# delay_width.net
KiCad netlist of a schematic drawn in Altium Designer
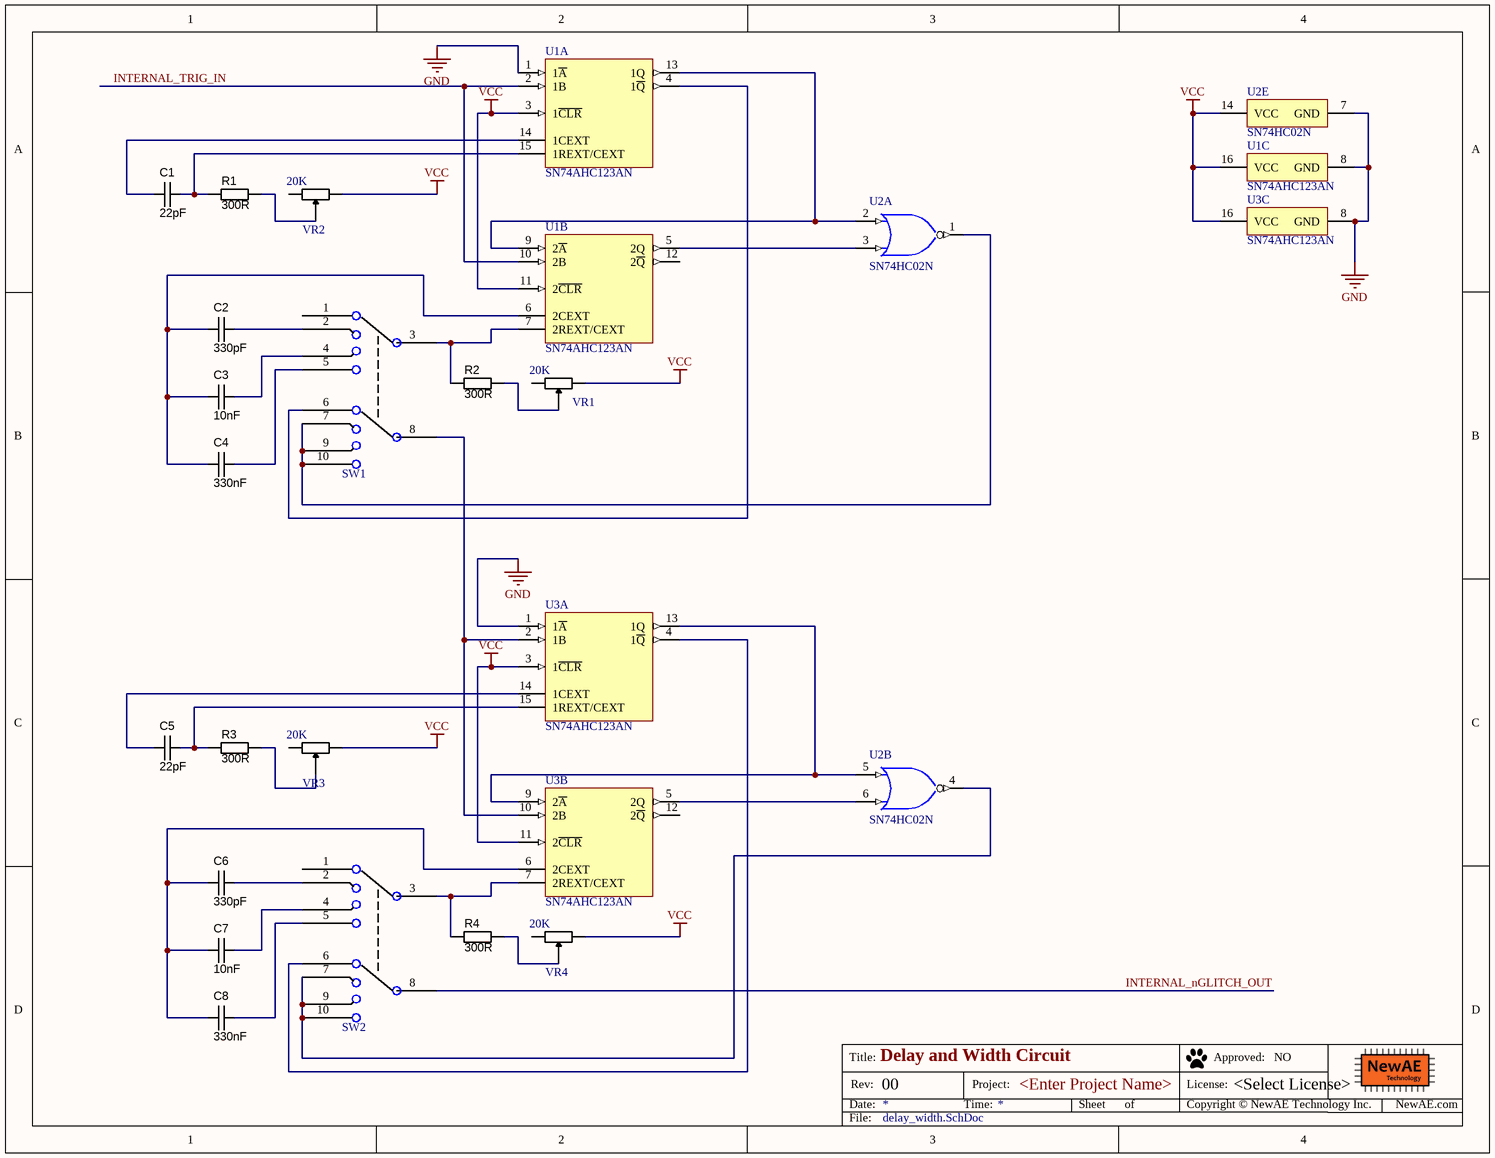
[diagram p0: delay_width.SchDoc]

(export (version "E")
  (design (tool "Eeschema 10.0.6"))
  (components
    (comp (ref "C1")
      (value "22pF")
      (footprint "CAPC500P450250X550")
      (description "Capacitor Ceramic 220nF 10% 50V X7R radial 5mm lead spacing")
      (fields (field (name "TOLERANCE") "±10%") (field (name "Comment") "approved sub OK"))
      (libsource (lib "PBL - Capacitors") (part "CAPR_220n_Radial_5mm"))
    )
    (comp (ref "C2")
      (value "330pF")
      (footprint "CAPC500P450250X550")
      (description "Capacitor Ceramic 220nF 10% 50V X7R radial 5mm lead spacing")
      (fields (field (name "TOLERANCE") "±10%") (field (name "Comment") "approved sub OK"))
      (libsource (lib "PBL - Capacitors") (part "CAPR_220n_Radial_5mm"))
    )
    (comp (ref "C3")
      (value "10nF")
      (footprint "CAPC500P450250X550")
      (description "Capacitor Ceramic 220nF 10% 50V X7R radial 5mm lead spacing")
      (fields (field (name "TOLERANCE") "±10%") (field (name "Comment") "approved sub OK"))
      (libsource (lib "PBL - Capacitors") (part "CAPR_220n_Radial_5mm"))
    )
    (comp (ref "C4")
      (value "330nF")
      (footprint "CAPC500P450250X550")
      (description "Capacitor Ceramic 220nF 10% 50V X7R radial 5mm lead spacing")
      (fields (field (name "TOLERANCE") "±10%") (field (name "Comment") "approved sub OK"))
      (libsource (lib "PBL - Capacitors") (part "CAPR_220n_Radial_5mm"))
    )
    (comp (ref "C5")
      (value "22pF")
      (footprint "CAPC500P450250X550")
      (description "Capacitor Ceramic 220nF 10% 50V X7R radial 5mm lead spacing")
      (fields (field (name "TOLERANCE") "±10%") (field (name "Comment") "approved sub OK"))
      (libsource (lib "PBL - Capacitors") (part "CAPR_220n_Radial_5mm"))
    )
    (comp (ref "C6")
      (value "330pF")
      (footprint "CAPC500P450250X550")
      (description "Capacitor Ceramic 220nF 10% 50V X7R radial 5mm lead spacing")
      (fields (field (name "TOLERANCE") "±10%") (field (name "Comment") "approved sub OK"))
      (libsource (lib "PBL - Capacitors") (part "CAPR_220n_Radial_5mm"))
    )
    (comp (ref "C7")
      (value "10nF")
      (footprint "CAPC500P450250X550")
      (description "Capacitor Ceramic 220nF 10% 50V X7R radial 5mm lead spacing")
      (fields (field (name "TOLERANCE") "±10%") (field (name "Comment") "approved sub OK"))
      (libsource (lib "PBL - Capacitors") (part "CAPR_220n_Radial_5mm"))
    )
    (comp (ref "C8")
      (value "330nF")
      (footprint "CAPC500P450250X550")
      (description "Capacitor Ceramic 220nF 10% 50V X7R radial 5mm lead spacing")
      (fields (field (name "TOLERANCE") "±10%") (field (name "Comment") "approved sub OK"))
      (libsource (lib "PBL - Capacitors") (part "CAPR_220n_Radial_5mm"))
    )
    (comp (ref "R1")
      (value "300R")
      (footprint "RESTH_AXIAL-0.4")
      (description "Resistor THD Axial 220 Ohm 0.25W 5% Carbon Film")
      (fields (field (name "TOLERANCE") "±5%") (field (name "Comment") "Carbon Film"))
      (libsource (lib "PBL - Resistors") (part "RES_220R_Axial_0.25W_5%"))
    )
    (comp (ref "R2")
      (value "300R")
      (footprint "RESTH_AXIAL-0.4")
      (description "Resistor THD Axial 220 Ohm 0.25W 5% Carbon Film")
      (fields (field (name "TOLERANCE") "±5%") (field (name "Comment") "Carbon Film"))
      (libsource (lib "PBL - Resistors") (part "RES_220R_Axial_0.25W_5%"))
    )
    (comp (ref "R3")
      (value "300R")
      (footprint "RESTH_AXIAL-0.4")
      (description "Resistor THD Axial 220 Ohm 0.25W 5% Carbon Film")
      (fields (field (name "TOLERANCE") "±5%") (field (name "Comment") "Carbon Film"))
      (libsource (lib "PBL - Resistors") (part "RES_220R_Axial_0.25W_5%"))
    )
    (comp (ref "R4")
      (value "300R")
      (footprint "RESTH_AXIAL-0.4")
      (description "Resistor THD Axial 220 Ohm 0.25W 5% Carbon Film")
      (fields (field (name "TOLERANCE") "±5%") (field (name "Comment") "Carbon Film"))
      (libsource (lib "PBL - Resistors") (part "RES_220R_Axial_0.25W_5%"))
    )
    (comp (ref "SW1")
      (value "SS-24E06-TG 5 (P)")
      (footprint "CK_SS24E06TG5P")
      (description "2P4T Slide, C&K Through Hole")
      (fields (field (name "PART NUMBER") "SS24E06TG5P"))
      (libsource (lib "NewAE_AltiumLib") (part "SW_2P4T_SS24E06TG5P"))
    )
    (comp (ref "SW2")
      (value "SS-24E06-TG 5 (P)")
      (footprint "CK_SS24E06TG5P")
      (description "2P4T Slide, C&K Through Hole")
      (fields (field (name "PART NUMBER") "SS24E06TG5P"))
      (libsource (lib "NewAE_AltiumLib") (part "SW_2P4T_SS24E06TG5P"))
    )
    (comp (ref "U1")
      (value "SN74AHC123AN")
      (footprint "N0016A")
      (description "Dual Retriggerable Monostable Multivibrators, N0016A, TUBE")
      (fields
        (field (name "GENERIC PART NUMBER") "SN74AHC123A")
        (field (name "MANUFACTURER") "Texas Instruments")
      )
      (libsource (lib "Altium Content Vault") (part "TI-SNX4XXXX123A_74LV221A-16"))
    )
    (comp (ref "U2")
      (value "SN74HC02N")
      (footprint "N0014A")
      (description "Quadruple 2-Input Positive-NOR Gates, N0014A, TUBE")
      (fields
        (field (name "MANUFACTURER") "Texas Instruments")
        (field (name "GENERIC PART NUMBER") "SN74HC02")
      )
      (libsource (lib "Altium Content Vault") (part "TI-NOR-4-2IN-14"))
    )
    (comp (ref "U3")
      (value "SN74AHC123AN")
      (footprint "N0016A")
      (description "Dual Retriggerable Monostable Multivibrators, N0016A, TUBE")
      (fields
        (field (name "GENERIC PART NUMBER") "SN74AHC123A")
        (field (name "MANUFACTURER") "Texas Instruments")
      )
      (libsource (lib "Altium Content Vault") (part "TI-SNX4XXXX123A_74LV221A-16"))
    )
    (comp (ref "VR1")
      (value "20K")
      (footprint "RES_PDB18")
      (description "POT 1/5W CARBON LINEAR VAR RESISTOR")
      (fields (field (name "PART NUMBER") "POT_PDB181"))
      (libsource (lib "NewAE_AltiumLib") (part "Potentiometer"))
    )
    (comp (ref "VR2")
      (value "20K")
      (footprint "RES_PDB18")
      (description "POT 1/5W CARBON LINEAR VAR RESISTOR")
      (fields (field (name "PART NUMBER") "POT_PDB181"))
      (libsource (lib "NewAE_AltiumLib") (part "Potentiometer"))
    )
    (comp (ref "VR3")
      (value "20K")
      (footprint "RES_PDB18")
      (description "POT 1/5W CARBON LINEAR VAR RESISTOR")
      (fields (field (name "PART NUMBER") "POT_PDB181"))
      (libsource (lib "NewAE_AltiumLib") (part "Potentiometer"))
    )
    (comp (ref "VR4")
      (value "20K")
      (footprint "RES_PDB18")
      (description "POT 1/5W CARBON LINEAR VAR RESISTOR")
      (fields (field (name "PART NUMBER") "POT_PDB181"))
      (libsource (lib "NewAE_AltiumLib") (part "Potentiometer"))
    )
  )
  (nets
    (net (code "1") (name "/INTERNAL_TRIG_IN") (class "Default")
      (node (ref "U1") (pin "10") (pinfunction "2B_10") (pintype "input"))
      (node (ref "U1") (pin "2") (pinfunction "1B_2") (pintype "input"))
    )
    (net (code "2") (name "/INTERNAL_nGLITCH_OUT") (class "Default")
      (node (ref "SW2") (pin "8") (pinfunction "8_8") (pintype "passive"))
    )
    (net (code "3") (name "GND") (class "Default")
      (node (ref "U1") (pin "1") (pinfunction "1~{A}_1") (pintype "input"))
      (node (ref "U1") (pin "8") (pinfunction "GND_8") (pintype "power_in"))
      (node (ref "U2") (pin "7") (pinfunction "GND_7") (pintype "power_in"))
      (node (ref "U3") (pin "1") (pinfunction "1~{A}_1") (pintype "input"))
      (node (ref "U3") (pin "8") (pinfunction "GND_8") (pintype "power_in"))
    )
    (net (code "4") (name "Net-(C2-Pad2)") (class "Default")
      (node (ref "C2") (pin "2") (pintype "passive"))
      (node (ref "SW1") (pin "2") (pinfunction "2_2") (pintype "passive"))
    )
    (net (code "5") (name "Net-(C3-Pad2)") (class "Default")
      (node (ref "C3") (pin "2") (pintype "passive"))
      (node (ref "SW1") (pin "4") (pinfunction "4_4") (pintype "passive"))
    )
    (net (code "6") (name "Net-(C4-Pad2)") (class "Default")
      (node (ref "C4") (pin "2") (pintype "passive"))
      (node (ref "SW1") (pin "5") (pinfunction "5_5") (pintype "passive"))
    )
    (net (code "7") (name "Net-(C6-Pad2)") (class "Default")
      (node (ref "C6") (pin "2") (pintype "passive"))
      (node (ref "SW2") (pin "2") (pinfunction "2_2") (pintype "passive"))
    )
    (net (code "8") (name "Net-(C7-Pad2)") (class "Default")
      (node (ref "C7") (pin "2") (pintype "passive"))
      (node (ref "SW2") (pin "4") (pinfunction "4_4") (pintype "passive"))
    )
    (net (code "9") (name "Net-(C8-Pad2)") (class "Default")
      (node (ref "C8") (pin "2") (pintype "passive"))
      (node (ref "SW2") (pin "5") (pinfunction "5_5") (pintype "passive"))
    )
    (net (code "10") (name "Net-(R1-Pad2)") (class "Default")
      (node (ref "R1") (pin "2") (pinfunction "2_2") (pintype "passive"))
      (node (ref "VR2") (pin "2") (pinfunction "2_2") (pintype "passive"))
    )
    (net (code "11") (name "Net-(R2-Pad2)") (class "Default")
      (node (ref "R2") (pin "2") (pinfunction "2_2") (pintype "passive"))
      (node (ref "VR1") (pin "2") (pinfunction "2_2") (pintype "passive"))
    )
    (net (code "12") (name "Net-(R3-Pad2)") (class "Default")
      (node (ref "R3") (pin "2") (pinfunction "2_2") (pintype "passive"))
      (node (ref "VR3") (pin "2") (pinfunction "2_2") (pintype "passive"))
    )
    (net (code "13") (name "Net-(R4-Pad2)") (class "Default")
      (node (ref "R4") (pin "2") (pinfunction "2_2") (pintype "passive"))
      (node (ref "VR4") (pin "2") (pinfunction "2_2") (pintype "passive"))
    )
    (net (code "14") (name "Net-(U1A-1CEXT)") (class "Default")
      (node (ref "C1") (pin "1") (pintype "passive"))
      (node (ref "U1") (pin "14") (pinfunction "1CEXT_14") (pintype "passive"))
    )
    (net (code "15") (name "Net-(U1A-1Q)") (class "Default")
      (node (ref "U1") (pin "13") (pinfunction "1Q_13") (pintype "output"))
      (node (ref "U1") (pin "9") (pinfunction "2~{A}_9") (pintype "input"))
      (node (ref "U2") (pin "2") (pinfunction "1A_2") (pintype "input"))
    )
    (net (code "16") (name "Net-(U1A-1REXT{slash}CEXT)") (class "Default")
      (node (ref "C1") (pin "2") (pintype "passive"))
      (node (ref "R1") (pin "1") (pinfunction "1_1") (pintype "passive"))
      (node (ref "U1") (pin "15") (pinfunction "1REXT/CEXT_15") (pintype "passive"))
    )
    (net (code "17") (name "Net-(U1A-1~{Q})") (class "Default")
      (node (ref "SW1") (pin "6") (pinfunction "6_6") (pintype "passive"))
      (node (ref "U1") (pin "4") (pinfunction "1~{Q}_4") (pintype "output"))
    )
    (net (code "18") (name "Net-(U1B-2CEXT)") (class "Default")
      (node (ref "C2") (pin "1") (pintype "passive"))
      (node (ref "C3") (pin "1") (pintype "passive"))
      (node (ref "C4") (pin "1") (pintype "passive"))
      (node (ref "U1") (pin "6") (pinfunction "2CEXT_6") (pintype "passive"))
    )
    (net (code "19") (name "Net-(U1B-2Q)") (class "Default")
      (node (ref "U1") (pin "5") (pinfunction "2Q_5") (pintype "output"))
      (node (ref "U2") (pin "3") (pinfunction "1B_3") (pintype "input"))
    )
    (net (code "20") (name "Net-(U1B-2REXT{slash}CEXT)") (class "Default")
      (node (ref "R2") (pin "1") (pinfunction "1_1") (pintype "passive"))
      (node (ref "SW1") (pin "3") (pinfunction "3_3") (pintype "passive"))
      (node (ref "U1") (pin "7") (pinfunction "2REXT/CEXT_7") (pintype "passive"))
    )
    (net (code "21") (name "Net-(U2A-1Y)") (class "Default")
      (node (ref "SW1") (pin "10") (pinfunction "10_10") (pintype "passive"))
      (node (ref "SW1") (pin "7") (pinfunction "7_7") (pintype "passive"))
      (node (ref "SW1") (pin "9") (pinfunction "9_9") (pintype "passive"))
      (node (ref "U2") (pin "1") (pinfunction "1Y_1") (pintype "output"))
    )
    (net (code "22") (name "Net-(U2B-2A)") (class "Default")
      (node (ref "U2") (pin "5") (pinfunction "2A_5") (pintype "input"))
      (node (ref "U3") (pin "13") (pinfunction "1Q_13") (pintype "output"))
      (node (ref "U3") (pin "9") (pinfunction "2~{A}_9") (pintype "input"))
    )
    (net (code "23") (name "Net-(U2B-2B)") (class "Default")
      (node (ref "U2") (pin "6") (pinfunction "2B_6") (pintype "input"))
      (node (ref "U3") (pin "5") (pinfunction "2Q_5") (pintype "output"))
    )
    (net (code "24") (name "Net-(U2B-2Y)") (class "Default")
      (node (ref "SW2") (pin "10") (pinfunction "10_10") (pintype "passive"))
      (node (ref "SW2") (pin "7") (pinfunction "7_7") (pintype "passive"))
      (node (ref "SW2") (pin "9") (pinfunction "9_9") (pintype "passive"))
      (node (ref "U2") (pin "4") (pinfunction "2Y_4") (pintype "output"))
    )
    (net (code "25") (name "Net-(U3A-1B)") (class "Default")
      (node (ref "SW1") (pin "8") (pinfunction "8_8") (pintype "passive"))
      (node (ref "U3") (pin "10") (pinfunction "2B_10") (pintype "input"))
      (node (ref "U3") (pin "2") (pinfunction "1B_2") (pintype "input"))
    )
    (net (code "26") (name "Net-(U3A-1CEXT)") (class "Default")
      (node (ref "C5") (pin "1") (pintype "passive"))
      (node (ref "U3") (pin "14") (pinfunction "1CEXT_14") (pintype "passive"))
    )
    (net (code "27") (name "Net-(U3A-1REXT{slash}CEXT)") (class "Default")
      (node (ref "C5") (pin "2") (pintype "passive"))
      (node (ref "R3") (pin "1") (pinfunction "1_1") (pintype "passive"))
      (node (ref "U3") (pin "15") (pinfunction "1REXT/CEXT_15") (pintype "passive"))
    )
    (net (code "28") (name "Net-(U3A-1~{Q})") (class "Default")
      (node (ref "SW2") (pin "6") (pinfunction "6_6") (pintype "passive"))
      (node (ref "U3") (pin "4") (pinfunction "1~{Q}_4") (pintype "output"))
    )
    (net (code "29") (name "Net-(U3B-2CEXT)") (class "Default")
      (node (ref "C6") (pin "1") (pintype "passive"))
      (node (ref "C7") (pin "1") (pintype "passive"))
      (node (ref "C8") (pin "1") (pintype "passive"))
      (node (ref "U3") (pin "6") (pinfunction "2CEXT_6") (pintype "passive"))
    )
    (net (code "30") (name "Net-(U3B-2REXT{slash}CEXT)") (class "Default")
      (node (ref "R4") (pin "1") (pinfunction "1_1") (pintype "passive"))
      (node (ref "SW2") (pin "3") (pinfunction "3_3") (pintype "passive"))
      (node (ref "U3") (pin "7") (pinfunction "2REXT/CEXT_7") (pintype "passive"))
    )
    (net (code "31") (name "VCC") (class "Default")
      (node (ref "U1") (pin "11") (pinfunction "2~{CLR}_11") (pintype "input"))
      (node (ref "U1") (pin "16") (pinfunction "VCC_16") (pintype "power_in"))
      (node (ref "U1") (pin "3") (pinfunction "1~{CLR}_3") (pintype "input"))
      (node (ref "U2") (pin "14") (pinfunction "VCC_14") (pintype "power_in"))
      (node (ref "U3") (pin "11") (pinfunction "2~{CLR}_11") (pintype "input"))
      (node (ref "U3") (pin "16") (pinfunction "VCC_16") (pintype "power_in"))
      (node (ref "U3") (pin "3") (pinfunction "1~{CLR}_3") (pintype "input"))
      (node (ref "VR1") (pin "1") (pinfunction "1_1") (pintype "passive"))
      (node (ref "VR2") (pin "1") (pinfunction "1_1") (pintype "passive"))
      (node (ref "VR3") (pin "1") (pinfunction "1_1") (pintype "passive"))
      (node (ref "VR4") (pin "1") (pinfunction "1_1") (pintype "passive"))
    )
    (net (code "32") (name "unconnected-(SW1-Pad1)") (class "Default")
      (node (ref "SW1") (pin "1") (pinfunction "1_1") (pintype "passive"))
    )
    (net (code "33") (name "unconnected-(SW2-Pad1)") (class "Default")
      (node (ref "SW2") (pin "1") (pinfunction "1_1") (pintype "passive"))
    )
    (net (code "34") (name "unconnected-(U1B-2~{Q}-Pad12)") (class "Default")
      (node (ref "U1") (pin "12") (pinfunction "2~{Q}_12") (pintype "output"))
    )
    (net (code "35") (name "unconnected-(U3B-2~{Q}-Pad12)") (class "Default")
      (node (ref "U3") (pin "12") (pinfunction "2~{Q}_12") (pintype "output"))
    )
    (net (code "36") (name "unconnected-(VR1-Pad3)") (class "Default")
      (node (ref "VR1") (pin "3") (pinfunction "3_3") (pintype "passive"))
    )
    (net (code "37") (name "unconnected-(VR2-Pad3)") (class "Default")
      (node (ref "VR2") (pin "3") (pinfunction "3_3") (pintype "passive"))
    )
    (net (code "38") (name "unconnected-(VR3-Pad3)") (class "Default")
      (node (ref "VR3") (pin "3") (pinfunction "3_3") (pintype "passive"))
    )
    (net (code "39") (name "unconnected-(VR4-Pad3)") (class "Default")
      (node (ref "VR4") (pin "3") (pinfunction "3_3") (pintype "passive"))
    )
  )
)
